# main4.net
KiCad netlist of a schematic drawn in EAGLE
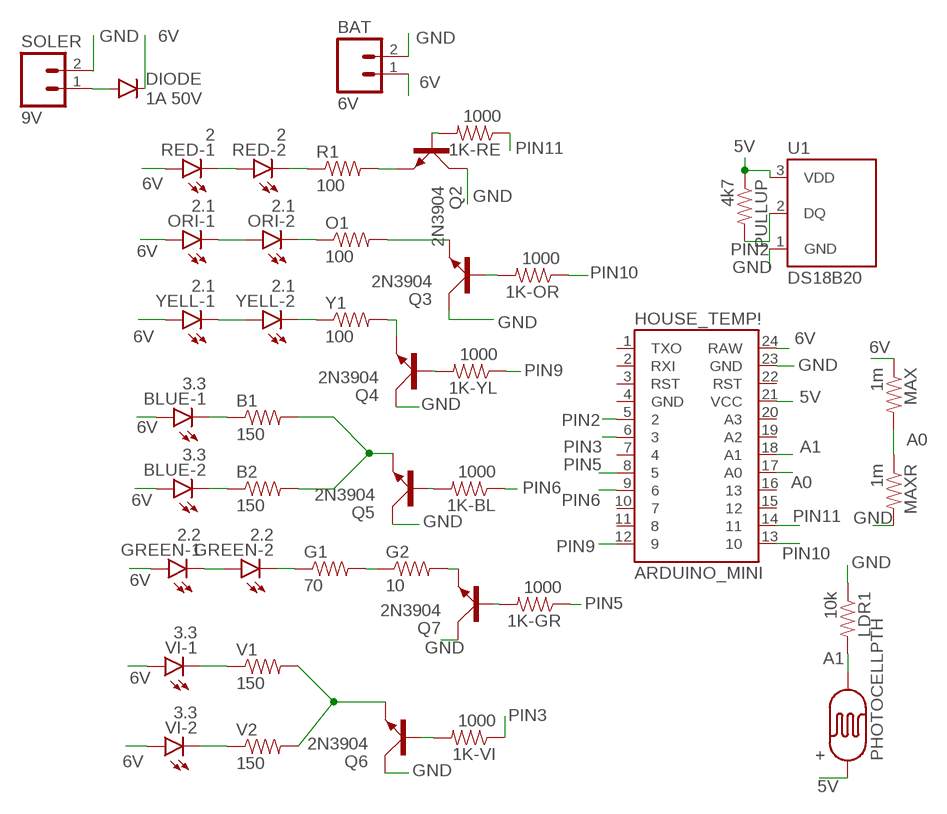
[diagram p0: schematic, sheet 1]

(export (version "E")
  (design (tool "Eeschema 10.0.6"))
  (components
    (comp (ref "+")
      (value "PHOTOCELLPTH")
      (footprint "eagle-import:PHOTOCELL")
      (libsource (lib "eagle-import") (part "PHOTOCELLPTH"))
    )
    (comp (ref "1K-BL")
      (value "1000")
      (footprint "eagle-import:AXIAL-0.3")
      (libsource (lib "eagle-import") (part "RESISTORAXIAL-0.3"))
    )
    (comp (ref "1K-GR")
      (value "1000")
      (footprint "eagle-import:AXIAL-0.3")
      (libsource (lib "eagle-import") (part "RESISTORAXIAL-0.3"))
    )
    (comp (ref "1K-OR")
      (value "1000")
      (footprint "eagle-import:AXIAL-0.3")
      (libsource (lib "eagle-import") (part "RESISTORAXIAL-0.3"))
    )
    (comp (ref "1K-RE")
      (value "1000")
      (footprint "eagle-import:AXIAL-0.3")
      (libsource (lib "eagle-import") (part "RESISTORAXIAL-0.3"))
    )
    (comp (ref "1K-VI")
      (value "1000")
      (footprint "eagle-import:AXIAL-0.3")
      (libsource (lib "eagle-import") (part "RESISTORAXIAL-0.3"))
    )
    (comp (ref "1K-YL")
      (value "1000")
      (footprint "eagle-import:AXIAL-0.3")
      (libsource (lib "eagle-import") (part "RESISTORAXIAL-0.3"))
    )
    (comp (ref "B1")
      (value "150")
      (footprint "eagle-import:AXIAL-0.3")
      (libsource (lib "eagle-import") (part "RESISTORAXIAL-0.3"))
    )
    (comp (ref "B2")
      (value "150")
      (footprint "eagle-import:AXIAL-0.3")
      (libsource (lib "eagle-import") (part "SparkFun-Resistors_RESISTORAXIAL-0.3"))
    )
    (comp (ref "BAT")
      (value "6V")
      (footprint "eagle-import:1X02")
      (libsource (lib "eagle-import") (part "M02PTH"))
    )
    (comp (ref "BLUE-1")
      (value "3.3")
      (footprint "eagle-import:LED10MM")
      (libsource (lib "eagle-import") (part "LED10MM"))
    )
    (comp (ref "BLUE-2")
      (value "3.3")
      (footprint "eagle-import:LED10MM")
      (libsource (lib "eagle-import") (part "LED10MM"))
    )
    (comp (ref "DIODE")
      (value "1A 50V")
      (footprint "eagle-import:DIODE-1N4001")
      (libsource (lib "eagle-import") (part "DIODEPTH"))
    )
    (comp (ref "G1")
      (value "70")
      (footprint "eagle-import:AXIAL-0.3")
      (libsource (lib "eagle-import") (part "SparkFun-Resistors_RESISTORAXIAL-0.3"))
    )
    (comp (ref "G2")
      (value "10")
      (footprint "eagle-import:AXIAL-0.3")
      (libsource (lib "eagle-import") (part "SparkFun-Resistors_RESISTORAXIAL-0.3"))
    )
    (comp (ref "GREEN-1")
      (value "2.2")
      (footprint "eagle-import:LED10MM")
      (libsource (lib "eagle-import") (part "LED10MM"))
    )
    (comp (ref "GREEN-2")
      (value "2.2")
      (footprint "eagle-import:LED10MM")
      (libsource (lib "eagle-import") (part "LED10MM"))
    )
    (comp (ref "HOUSE_TEMP!")
      (value "ARDUINO_MINI")
      (footprint "eagle-import:ARDUINO_MINI")
      (libsource (lib "eagle-import") (part "ARDUINO_MINI"))
    )
    (comp (ref "LDR1")
      (value "10k")
      (footprint "eagle-import:AXIAL-0.3")
      (libsource (lib "eagle-import") (part "SparkFun-Resistors_RESISTORAXIAL-0.3"))
    )
    (comp (ref "MAX")
      (value "1m")
      (footprint "eagle-import:AXIAL-0.3")
      (libsource (lib "eagle-import") (part "RESISTORAXIAL-0.3"))
    )
    (comp (ref "MAXR")
      (value "1m")
      (footprint "eagle-import:AXIAL-0.3")
      (libsource (lib "eagle-import") (part "RESISTORAXIAL-0.3"))
    )
    (comp (ref "O1")
      (value "100")
      (footprint "eagle-import:AXIAL-0.3")
      (libsource (lib "eagle-import") (part "RESISTORAXIAL-0.3"))
    )
    (comp (ref "ORI-1")
      (value "2.1")
      (footprint "eagle-import:LED10MM")
      (libsource (lib "eagle-import") (part "LED10MM"))
    )
    (comp (ref "ORI-2")
      (value "2.1")
      (footprint "eagle-import:LED10MM")
      (libsource (lib "eagle-import") (part "LED10MM"))
    )
    (comp (ref "PULLUP")
      (value "4k7")
      (footprint "eagle-import:AXIAL-0.3")
      (libsource (lib "eagle-import") (part "RESISTORAXIAL-0.3"))
    )
    (comp (ref "Q2")
      (value "2N3904")
      (footprint "eagle-import:TO92D")
      (libsource (lib "eagle-import") (part "2N3904"))
    )
    (comp (ref "Q3")
      (value "2N3904")
      (footprint "eagle-import:TO92D")
      (libsource (lib "eagle-import") (part "2N3904"))
    )
    (comp (ref "Q4")
      (value "2N3904")
      (footprint "eagle-import:TO92D")
      (libsource (lib "eagle-import") (part "2N3904"))
    )
    (comp (ref "Q5")
      (value "2N3904")
      (footprint "eagle-import:TO92D")
      (libsource (lib "eagle-import") (part "2N3904"))
    )
    (comp (ref "Q6")
      (value "2N3904")
      (footprint "eagle-import:TO92D")
      (libsource (lib "eagle-import") (part "2N3904"))
    )
    (comp (ref "Q7")
      (value "2N3904")
      (footprint "eagle-import:TO92D")
      (libsource (lib "eagle-import") (part "2N3904"))
    )
    (comp (ref "R1")
      (value "100")
      (footprint "eagle-import:AXIAL-0.3")
      (libsource (lib "eagle-import") (part "RESISTORAXIAL-0.3"))
    )
    (comp (ref "RED-1")
      (value "2")
      (footprint "eagle-import:LED10MM")
      (libsource (lib "eagle-import") (part "LED10MM"))
    )
    (comp (ref "RED-2")
      (value "2")
      (footprint "eagle-import:LED10MM")
      (libsource (lib "eagle-import") (part "LED10MM"))
    )
    (comp (ref "SOLER")
      (value "9V")
      (footprint "eagle-import:1X02")
      (libsource (lib "eagle-import") (part "M02PTH"))
    )
    (comp (ref "U1")
      (value "DS18B20")
      (footprint "eagle-import:TO-92-AMMO")
      (libsource (lib "eagle-import") (part "DS18B20"))
    )
    (comp (ref "V1")
      (value "150")
      (footprint "eagle-import:AXIAL-0.3")
      (libsource (lib "eagle-import") (part "RESISTORAXIAL-0.3"))
    )
    (comp (ref "V2")
      (value "150")
      (footprint "eagle-import:AXIAL-0.3")
      (libsource (lib "eagle-import") (part "SparkFun-Resistors_RESISTORAXIAL-0.3"))
    )
    (comp (ref "VI-1")
      (value "3.3")
      (footprint "eagle-import:LED10MM")
      (libsource (lib "eagle-import") (part "LED10MM"))
    )
    (comp (ref "VI-2")
      (value "3.3")
      (footprint "eagle-import:LED10MM")
      (libsource (lib "eagle-import") (part "LED10MM"))
    )
    (comp (ref "Y1")
      (value "100")
      (footprint "eagle-import:AXIAL-0.3")
      (libsource (lib "eagle-import") (part "RESISTORAXIAL-0.3"))
    )
    (comp (ref "YELL-1")
      (value "2.1")
      (footprint "eagle-import:LED10MM")
      (libsource (lib "eagle-import") (part "LED10MM"))
    )
    (comp (ref "YELL-2")
      (value "2.1")
      (footprint "eagle-import:LED10MM")
      (libsource (lib "eagle-import") (part "LED10MM"))
    )
  )
  (nets
    (net (code "1") (name "/5V") (class "Default")
      (node (ref "+") (pin "1") (pinfunction "P$1_1") (pintype "bidirectional"))
      (node (ref "HOUSE_TEMP!") (pin "21") (pinfunction "VCC_21") (pintype "bidirectional"))
      (node (ref "PULLUP") (pin "P$1") (pinfunction "1_P$1") (pintype "passive"))
      (node (ref "U1") (pin "3") (pinfunction "VDD_3") (pintype "power_in"))
    )
    (net (code "2") (name "/6V") (class "Default")
      (node (ref "BAT") (pin "1") (pinfunction "1_1") (pintype "passive"))
      (node (ref "BLUE-1") (pin "A") (pinfunction "A_A") (pintype "passive"))
      (node (ref "BLUE-2") (pin "A") (pinfunction "A_A") (pintype "passive"))
      (node (ref "DIODE") (pin "C") (pinfunction "C_C") (pintype "passive"))
      (node (ref "GREEN-1") (pin "A") (pinfunction "A_A") (pintype "passive"))
      (node (ref "HOUSE_TEMP!") (pin "24") (pinfunction "RAW_24") (pintype "bidirectional"))
      (node (ref "MAX") (pin "P$1") (pinfunction "1_P$1") (pintype "passive"))
      (node (ref "ORI-1") (pin "A") (pinfunction "A_A") (pintype "passive"))
      (node (ref "RED-1") (pin "A") (pinfunction "A_A") (pintype "passive"))
      (node (ref "VI-1") (pin "A") (pinfunction "A_A") (pintype "passive"))
      (node (ref "VI-2") (pin "A") (pinfunction "A_A") (pintype "passive"))
      (node (ref "YELL-1") (pin "A") (pinfunction "A_A") (pintype "passive"))
    )
    (net (code "3") (name "/A0") (class "Default")
      (node (ref "HOUSE_TEMP!") (pin "17") (pinfunction "A0_17") (pintype "bidirectional"))
      (node (ref "MAX") (pin "P$2") (pinfunction "2_P$2") (pintype "passive"))
      (node (ref "MAXR") (pin "P$1") (pinfunction "1_P$1") (pintype "passive"))
    )
    (net (code "4") (name "/A1") (class "Default")
      (node (ref "+") (pin "2") (pinfunction "P$2_2") (pintype "bidirectional"))
      (node (ref "HOUSE_TEMP!") (pin "18") (pinfunction "A1_18") (pintype "bidirectional"))
      (node (ref "LDR1") (pin "P$2") (pinfunction "2_P$2") (pintype "passive"))
    )
    (net (code "5") (name "/GND") (class "Default")
      (node (ref "BAT") (pin "2") (pinfunction "2_2") (pintype "passive"))
      (node (ref "HOUSE_TEMP!") (pin "23") (pinfunction "GND_23") (pintype "bidirectional"))
      (node (ref "LDR1") (pin "P$1") (pinfunction "1_P$1") (pintype "passive"))
      (node (ref "MAXR") (pin "P$2") (pinfunction "2_P$2") (pintype "passive"))
      (node (ref "Q2") (pin "C") (pinfunction "C_C") (pintype "passive"))
      (node (ref "Q3") (pin "C") (pinfunction "C_C") (pintype "passive"))
      (node (ref "Q4") (pin "C") (pinfunction "C_C") (pintype "passive"))
      (node (ref "Q5") (pin "C") (pinfunction "C_C") (pintype "passive"))
      (node (ref "Q6") (pin "C") (pinfunction "C_C") (pintype "passive"))
      (node (ref "Q7") (pin "C") (pinfunction "C_C") (pintype "passive"))
      (node (ref "SOLER") (pin "2") (pinfunction "2_2") (pintype "passive"))
      (node (ref "U1") (pin "1") (pinfunction "GND_1") (pintype "power_in"))
    )
    (net (code "6") (name "/PIN2") (class "Default")
      (node (ref "HOUSE_TEMP!") (pin "5") (pinfunction "2_5") (pintype "bidirectional"))
      (node (ref "PULLUP") (pin "P$2") (pinfunction "2_P$2") (pintype "passive"))
      (node (ref "U1") (pin "2") (pinfunction "DQ_2") (pintype "bidirectional"))
    )
    (net (code "7") (name "/PIN3") (class "Default")
      (node (ref "1K-VI") (pin "P$1") (pinfunction "1_P$1") (pintype "passive"))
      (node (ref "HOUSE_TEMP!") (pin "6") (pinfunction "3_6") (pintype "bidirectional"))
    )
    (net (code "8") (name "/PIN5") (class "Default")
      (node (ref "1K-GR") (pin "P$1") (pinfunction "1_P$1") (pintype "passive"))
      (node (ref "HOUSE_TEMP!") (pin "8") (pinfunction "5_8") (pintype "bidirectional"))
    )
    (net (code "9") (name "/PIN6") (class "Default")
      (node (ref "1K-BL") (pin "P$1") (pinfunction "1_P$1") (pintype "passive"))
      (node (ref "HOUSE_TEMP!") (pin "9") (pinfunction "6_9") (pintype "bidirectional"))
    )
    (net (code "10") (name "/PIN9") (class "Default")
      (node (ref "1K-YL") (pin "P$1") (pinfunction "1_P$1") (pintype "passive"))
      (node (ref "HOUSE_TEMP!") (pin "12") (pinfunction "9_12") (pintype "bidirectional"))
    )
    (net (code "11") (name "/PIN10") (class "Default")
      (node (ref "1K-OR") (pin "P$1") (pinfunction "1_P$1") (pintype "passive"))
      (node (ref "HOUSE_TEMP!") (pin "13") (pinfunction "10_13") (pintype "bidirectional"))
    )
    (net (code "12") (name "/PIN11") (class "Default")
      (node (ref "1K-RE") (pin "P$1") (pinfunction "1_P$1") (pintype "passive"))
      (node (ref "HOUSE_TEMP!") (pin "14") (pinfunction "11_14") (pintype "bidirectional"))
    )
    (net (code "13") (name "Net-(1K-BL-2)") (class "Default")
      (node (ref "1K-BL") (pin "P$2") (pinfunction "2_P$2") (pintype "passive"))
      (node (ref "Q5") (pin "B") (pinfunction "B_B") (pintype "passive"))
    )
    (net (code "14") (name "Net-(1K-GR-2)") (class "Default")
      (node (ref "1K-GR") (pin "P$2") (pinfunction "2_P$2") (pintype "passive"))
      (node (ref "Q7") (pin "B") (pinfunction "B_B") (pintype "passive"))
    )
    (net (code "15") (name "Net-(1K-OR-2)") (class "Default")
      (node (ref "1K-OR") (pin "P$2") (pinfunction "2_P$2") (pintype "passive"))
      (node (ref "Q3") (pin "B") (pinfunction "B_B") (pintype "passive"))
    )
    (net (code "16") (name "Net-(1K-RE-2)") (class "Default")
      (node (ref "1K-RE") (pin "P$2") (pinfunction "2_P$2") (pintype "passive"))
      (node (ref "Q2") (pin "B") (pinfunction "B_B") (pintype "passive"))
    )
    (net (code "17") (name "Net-(1K-VI-2)") (class "Default")
      (node (ref "1K-VI") (pin "P$2") (pinfunction "2_P$2") (pintype "passive"))
      (node (ref "Q6") (pin "B") (pinfunction "B_B") (pintype "passive"))
    )
    (net (code "18") (name "Net-(1K-YL-2)") (class "Default")
      (node (ref "1K-YL") (pin "P$2") (pinfunction "2_P$2") (pintype "passive"))
      (node (ref "Q4") (pin "B") (pinfunction "B_B") (pintype "passive"))
    )
    (net (code "19") (name "Net-(B1-1)") (class "Default")
      (node (ref "B1") (pin "P$1") (pinfunction "1_P$1") (pintype "passive"))
      (node (ref "BLUE-1") (pin "C") (pinfunction "C_C") (pintype "passive"))
    )
    (net (code "20") (name "Net-(B1-2)") (class "Default")
      (node (ref "B1") (pin "P$2") (pinfunction "2_P$2") (pintype "passive"))
      (node (ref "B2") (pin "P$2") (pinfunction "2_P$2") (pintype "passive"))
      (node (ref "Q5") (pin "E") (pinfunction "E_E") (pintype "passive"))
    )
    (net (code "21") (name "Net-(B2-1)") (class "Default")
      (node (ref "B2") (pin "P$1") (pinfunction "1_P$1") (pintype "passive"))
      (node (ref "BLUE-2") (pin "C") (pinfunction "C_C") (pintype "passive"))
    )
    (net (code "22") (name "Net-(DIODE-PadA)") (class "Default")
      (node (ref "DIODE") (pin "A") (pinfunction "A_A") (pintype "passive"))
      (node (ref "SOLER") (pin "1") (pinfunction "1_1") (pintype "passive"))
    )
    (net (code "23") (name "Net-(G1-1)") (class "Default")
      (node (ref "G1") (pin "P$1") (pinfunction "1_P$1") (pintype "passive"))
      (node (ref "GREEN-2") (pin "C") (pinfunction "C_C") (pintype "passive"))
    )
    (net (code "24") (name "Net-(G1-2)") (class "Default")
      (node (ref "G1") (pin "P$2") (pinfunction "2_P$2") (pintype "passive"))
      (node (ref "G2") (pin "P$1") (pinfunction "1_P$1") (pintype "passive"))
    )
    (net (code "25") (name "Net-(G2-2)") (class "Default")
      (node (ref "G2") (pin "P$2") (pinfunction "2_P$2") (pintype "passive"))
      (node (ref "Q7") (pin "E") (pinfunction "E_E") (pintype "passive"))
    )
    (net (code "26") (name "Net-(GREEN-1-PadC)") (class "Default")
      (node (ref "GREEN-1") (pin "C") (pinfunction "C_C") (pintype "passive"))
      (node (ref "GREEN-2") (pin "A") (pinfunction "A_A") (pintype "passive"))
    )
    (net (code "27") (name "Net-(O1-1)") (class "Default")
      (node (ref "O1") (pin "P$1") (pinfunction "1_P$1") (pintype "passive"))
      (node (ref "ORI-2") (pin "C") (pinfunction "C_C") (pintype "passive"))
    )
    (net (code "28") (name "Net-(O1-2)") (class "Default")
      (node (ref "O1") (pin "P$2") (pinfunction "2_P$2") (pintype "passive"))
      (node (ref "Q3") (pin "E") (pinfunction "E_E") (pintype "passive"))
    )
    (net (code "29") (name "Net-(ORI-1-PadC)") (class "Default")
      (node (ref "ORI-1") (pin "C") (pinfunction "C_C") (pintype "passive"))
      (node (ref "ORI-2") (pin "A") (pinfunction "A_A") (pintype "passive"))
    )
    (net (code "30") (name "Net-(R1-1)") (class "Default")
      (node (ref "R1") (pin "P$1") (pinfunction "1_P$1") (pintype "passive"))
      (node (ref "RED-2") (pin "C") (pinfunction "C_C") (pintype "passive"))
    )
    (net (code "31") (name "Net-(R1-2)") (class "Default")
      (node (ref "Q2") (pin "E") (pinfunction "E_E") (pintype "passive"))
      (node (ref "R1") (pin "P$2") (pinfunction "2_P$2") (pintype "passive"))
    )
    (net (code "32") (name "Net-(RED-1-PadC)") (class "Default")
      (node (ref "RED-1") (pin "C") (pinfunction "C_C") (pintype "passive"))
      (node (ref "RED-2") (pin "A") (pinfunction "A_A") (pintype "passive"))
    )
    (net (code "33") (name "Net-(V1-1)") (class "Default")
      (node (ref "V1") (pin "P$1") (pinfunction "1_P$1") (pintype "passive"))
      (node (ref "VI-1") (pin "C") (pinfunction "C_C") (pintype "passive"))
    )
    (net (code "34") (name "Net-(V1-2)") (class "Default")
      (node (ref "Q6") (pin "E") (pinfunction "E_E") (pintype "passive"))
      (node (ref "V1") (pin "P$2") (pinfunction "2_P$2") (pintype "passive"))
      (node (ref "V2") (pin "P$2") (pinfunction "2_P$2") (pintype "passive"))
    )
    (net (code "35") (name "Net-(V2-1)") (class "Default")
      (node (ref "V2") (pin "P$1") (pinfunction "1_P$1") (pintype "passive"))
      (node (ref "VI-2") (pin "C") (pinfunction "C_C") (pintype "passive"))
    )
    (net (code "36") (name "Net-(Y1-1)") (class "Default")
      (node (ref "Y1") (pin "P$1") (pinfunction "1_P$1") (pintype "passive"))
      (node (ref "YELL-2") (pin "C") (pinfunction "C_C") (pintype "passive"))
    )
    (net (code "37") (name "Net-(Y1-2)") (class "Default")
      (node (ref "Q4") (pin "E") (pinfunction "E_E") (pintype "passive"))
      (node (ref "Y1") (pin "P$2") (pinfunction "2_P$2") (pintype "passive"))
    )
    (net (code "38") (name "Net-(YELL-1-PadC)") (class "Default")
      (node (ref "YELL-1") (pin "C") (pinfunction "C_C") (pintype "passive"))
      (node (ref "YELL-2") (pin "A") (pinfunction "A_A") (pintype "passive"))
    )
    (net (code "39") (name "unconnected-(HOUSE_TEMP!-4-Pad7)") (class "Default")
      (node (ref "HOUSE_TEMP!") (pin "7") (pinfunction "4_7") (pintype "bidirectional"))
    )
    (net (code "40") (name "unconnected-(HOUSE_TEMP!-7-Pad10)") (class "Default")
      (node (ref "HOUSE_TEMP!") (pin "10") (pinfunction "7_10") (pintype "bidirectional"))
    )
    (net (code "41") (name "unconnected-(HOUSE_TEMP!-8-Pad11)") (class "Default")
      (node (ref "HOUSE_TEMP!") (pin "11") (pinfunction "8_11") (pintype "bidirectional"))
    )
    (net (code "42") (name "unconnected-(HOUSE_TEMP!-12-Pad15)") (class "Default")
      (node (ref "HOUSE_TEMP!") (pin "15") (pinfunction "12_15") (pintype "bidirectional"))
    )
    (net (code "43") (name "unconnected-(HOUSE_TEMP!-13-Pad16)") (class "Default")
      (node (ref "HOUSE_TEMP!") (pin "16") (pinfunction "13_16") (pintype "bidirectional"))
    )
    (net (code "44") (name "unconnected-(HOUSE_TEMP!-A2-Pad19)") (class "Default")
      (node (ref "HOUSE_TEMP!") (pin "19") (pinfunction "A2_19") (pintype "bidirectional"))
    )
    (net (code "45") (name "unconnected-(HOUSE_TEMP!-A3-Pad20)") (class "Default")
      (node (ref "HOUSE_TEMP!") (pin "20") (pinfunction "A3_20") (pintype "bidirectional"))
    )
    (net (code "46") (name "unconnected-(HOUSE_TEMP!-GND-Pad4)") (class "Default")
      (node (ref "HOUSE_TEMP!") (pin "4") (pinfunction "GND_4") (pintype "bidirectional"))
    )
    (net (code "47") (name "unconnected-(HOUSE_TEMP!-RST-Pad3)") (class "Default")
      (node (ref "HOUSE_TEMP!") (pin "3") (pinfunction "RST_3") (pintype "bidirectional"))
    )
    (net (code "48") (name "unconnected-(HOUSE_TEMP!-RST-Pad22)") (class "Default")
      (node (ref "HOUSE_TEMP!") (pin "22") (pinfunction "RST_22") (pintype "bidirectional"))
    )
    (net (code "49") (name "unconnected-(HOUSE_TEMP!-RXI-Pad2)") (class "Default")
      (node (ref "HOUSE_TEMP!") (pin "2") (pinfunction "RXI_2") (pintype "bidirectional"))
    )
    (net (code "50") (name "unconnected-(HOUSE_TEMP!-TXO-Pad1)") (class "Default")
      (node (ref "HOUSE_TEMP!") (pin "1") (pinfunction "TXO_1") (pintype "bidirectional"))
    )
  )
)
